# main.net
KiCad netlist of a schematic drawn in EAGLE
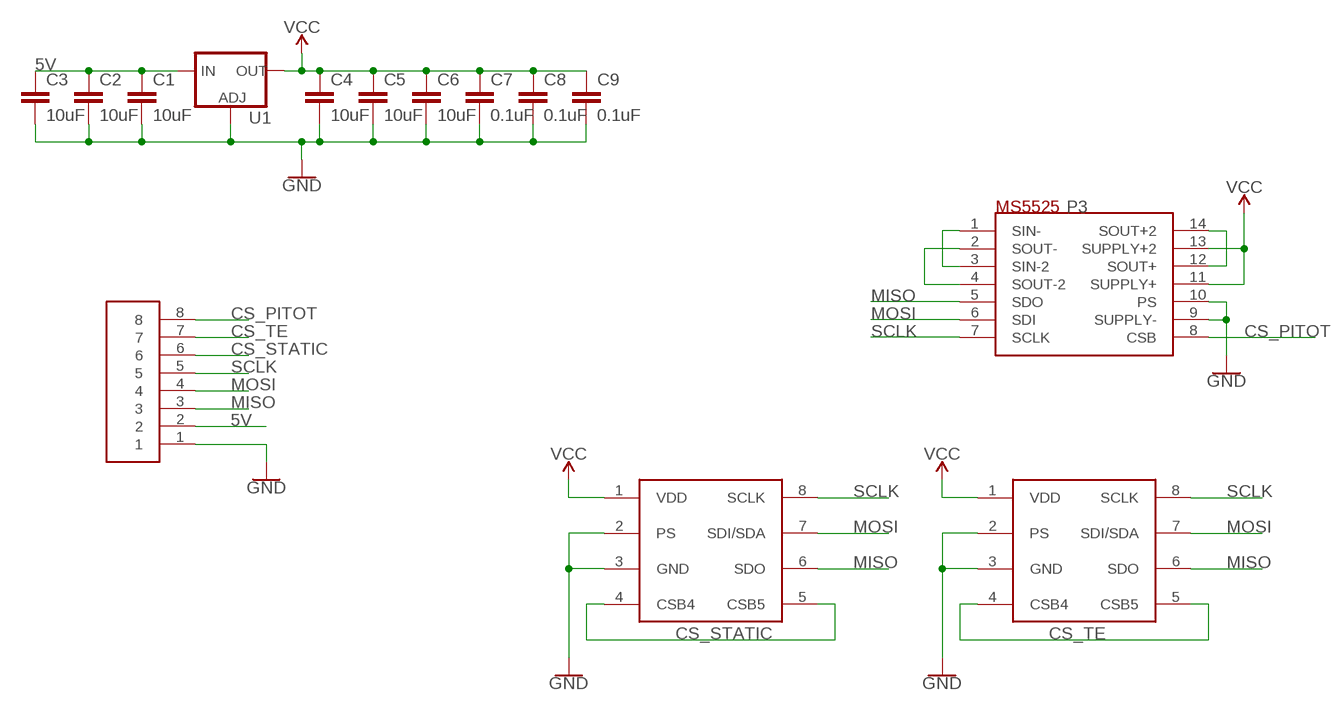
[diagram p0: schematic, sheet 1]

(export (version "E")
  (design (tool "Eeschema 10.0.6"))
  (components
    (comp (ref "C1")
      (value "10uF")
      (footprint "eagle-import:0805")
      (libsource (lib "eagle-import") (part "10UF-0805-10V-10%"))
    )
    (comp (ref "C2")
      (value "10uF")
      (footprint "eagle-import:0805")
      (libsource (lib "eagle-import") (part "10UF-0805-10V-10%"))
    )
    (comp (ref "C3")
      (value "10uF")
      (footprint "eagle-import:0805")
      (libsource (lib "eagle-import") (part "10UF-0805-10V-10%"))
    )
    (comp (ref "C4")
      (value "10uF")
      (footprint "eagle-import:0805")
      (libsource (lib "eagle-import") (part "10UF-0805-10V-10%"))
    )
    (comp (ref "C5")
      (value "10uF")
      (footprint "eagle-import:0805")
      (libsource (lib "eagle-import") (part "10UF-0805-10V-10%"))
    )
    (comp (ref "C6")
      (value "10uF")
      (footprint "eagle-import:0805")
      (libsource (lib "eagle-import") (part "10UF-0805-10V-10%"))
    )
    (comp (ref "C7")
      (value "0.1uF")
      (footprint "eagle-import:0603")
      (libsource (lib "eagle-import") (part "0.1UF-0603-25V-5%"))
    )
    (comp (ref "C8")
      (value "0.1uF")
      (footprint "eagle-import:0603")
      (libsource (lib "eagle-import") (part "0.1UF-0603-25V-5%"))
    )
    (comp (ref "C9")
      (value "0.1uF")
      (footprint "eagle-import:0603")
      (libsource (lib "eagle-import") (part "0.1UF-0603-25V-5%"))
    )
    (comp (ref "P1")
      (value "MS5611")
      (footprint "eagle-import:MS5611")
      (libsource (lib "eagle-import") (part "MS5611"))
    )
    (comp (ref "P2")
      (value "MS5611")
      (footprint "eagle-import:MS5611")
      (libsource (lib "eagle-import") (part "MS5611"))
    )
    (comp (ref "P3")
      (value "MS5525")
      (footprint "eagle-import:SOIC14-WIDE")
      (libsource (lib "eagle-import") (part "MS5525"))
    )
    (comp (ref "U$1")
      (value "HEADER8")
      (footprint "eagle-import:8PINVALULOK")
      (libsource (lib "eagle-import") (part "HEADER8"))
    )
    (comp (ref "U1")
      (value "V_REG_317SMD")
      (footprint "eagle-import:SOT223")
      (libsource (lib "eagle-import") (part "V_REG_317SMD"))
    )
  )
  (nets
    (net (code "1") (name "/5V") (class "Default")
      (node (ref "C1") (pin "1") (pinfunction "1_1") (pintype "passive"))
      (node (ref "C2") (pin "1") (pinfunction "1_1") (pintype "passive"))
      (node (ref "C3") (pin "1") (pinfunction "1_1") (pintype "passive"))
      (node (ref "U$1") (pin "2") (pinfunction "2_2") (pintype "bidirectional"))
      (node (ref "U1") (pin "3") (pinfunction "IN_3") (pintype "input"))
    )
    (net (code "2") (name "/CS_PITOT") (class "Default")
      (node (ref "P3") (pin "8") (pinfunction "CSB_8") (pintype "bidirectional"))
      (node (ref "U$1") (pin "8") (pinfunction "8_8") (pintype "bidirectional"))
    )
    (net (code "3") (name "/CS_STATIC") (class "Default")
      (node (ref "P1") (pin "4") (pinfunction "CSB4_4") (pintype "bidirectional"))
      (node (ref "P1") (pin "5") (pinfunction "CSB5_5") (pintype "bidirectional"))
      (node (ref "U$1") (pin "6") (pinfunction "6_6") (pintype "bidirectional"))
    )
    (net (code "4") (name "/CS_TE") (class "Default")
      (node (ref "P2") (pin "4") (pinfunction "CSB4_4") (pintype "bidirectional"))
      (node (ref "P2") (pin "5") (pinfunction "CSB5_5") (pintype "bidirectional"))
      (node (ref "U$1") (pin "7") (pinfunction "7_7") (pintype "bidirectional"))
    )
    (net (code "5") (name "/MISO") (class "Default")
      (node (ref "P1") (pin "6") (pinfunction "SDO_6") (pintype "bidirectional"))
      (node (ref "P2") (pin "6") (pinfunction "SDO_6") (pintype "bidirectional"))
      (node (ref "P3") (pin "5") (pinfunction "SDO_5") (pintype "bidirectional"))
      (node (ref "U$1") (pin "3") (pinfunction "3_3") (pintype "bidirectional"))
    )
    (net (code "6") (name "/MOSI") (class "Default")
      (node (ref "P1") (pin "7") (pinfunction "SDI/SDA_7") (pintype "bidirectional"))
      (node (ref "P2") (pin "7") (pinfunction "SDI/SDA_7") (pintype "bidirectional"))
      (node (ref "P3") (pin "6") (pinfunction "SDI_6") (pintype "bidirectional"))
      (node (ref "U$1") (pin "4") (pinfunction "4_4") (pintype "bidirectional"))
    )
    (net (code "7") (name "/SCLK") (class "Default")
      (node (ref "P1") (pin "8") (pinfunction "SCLK_8") (pintype "bidirectional"))
      (node (ref "P2") (pin "8") (pinfunction "SCLK_8") (pintype "bidirectional"))
      (node (ref "P3") (pin "7") (pinfunction "SCLK_7") (pintype "bidirectional"))
      (node (ref "U$1") (pin "5") (pinfunction "5_5") (pintype "bidirectional"))
    )
    (net (code "8") (name "GND") (class "Default")
      (node (ref "C1") (pin "2") (pinfunction "2_2") (pintype "passive"))
      (node (ref "C2") (pin "2") (pinfunction "2_2") (pintype "passive"))
      (node (ref "C3") (pin "2") (pinfunction "2_2") (pintype "passive"))
      (node (ref "C4") (pin "2") (pinfunction "2_2") (pintype "passive"))
      (node (ref "C5") (pin "2") (pinfunction "2_2") (pintype "passive"))
      (node (ref "C6") (pin "2") (pinfunction "2_2") (pintype "passive"))
      (node (ref "C7") (pin "2") (pinfunction "2_2") (pintype "passive"))
      (node (ref "C8") (pin "2") (pinfunction "2_2") (pintype "passive"))
      (node (ref "C9") (pin "2") (pinfunction "2_2") (pintype "passive"))
      (node (ref "P1") (pin "2") (pinfunction "PS_2") (pintype "bidirectional"))
      (node (ref "P1") (pin "3") (pinfunction "GND_3") (pintype "bidirectional"))
      (node (ref "P2") (pin "2") (pinfunction "PS_2") (pintype "bidirectional"))
      (node (ref "P2") (pin "3") (pinfunction "GND_3") (pintype "bidirectional"))
      (node (ref "P3") (pin "10") (pinfunction "PS_10") (pintype "bidirectional"))
      (node (ref "P3") (pin "9") (pinfunction "SUPPLY-_9") (pintype "bidirectional"))
      (node (ref "U$1") (pin "1") (pinfunction "1_1") (pintype "bidirectional"))
      (node (ref "U1") (pin "1") (pinfunction "ADJ_1") (pintype "input"))
    )
    (net (code "9") (name "Net-(P3-SIN-)") (class "Default")
      (node (ref "P3") (pin "1") (pinfunction "SIN-_1") (pintype "bidirectional"))
      (node (ref "P3") (pin "3") (pinfunction "SIN-2_3") (pintype "bidirectional"))
    )
    (net (code "10") (name "Net-(P3-SOUT+)") (class "Default")
      (node (ref "P3") (pin "12") (pinfunction "SOUT+_12") (pintype "bidirectional"))
      (node (ref "P3") (pin "14") (pinfunction "SOUT+2_14") (pintype "bidirectional"))
    )
    (net (code "11") (name "Net-(P3-SOUT-)") (class "Default")
      (node (ref "P3") (pin "2") (pinfunction "SOUT-_2") (pintype "bidirectional"))
      (node (ref "P3") (pin "4") (pinfunction "SOUT-2_4") (pintype "bidirectional"))
    )
    (net (code "12") (name "VCC") (class "Default")
      (node (ref "C4") (pin "1") (pinfunction "1_1") (pintype "passive"))
      (node (ref "C5") (pin "1") (pinfunction "1_1") (pintype "passive"))
      (node (ref "C6") (pin "1") (pinfunction "1_1") (pintype "passive"))
      (node (ref "C7") (pin "1") (pinfunction "1_1") (pintype "passive"))
      (node (ref "C8") (pin "1") (pinfunction "1_1") (pintype "passive"))
      (node (ref "C9") (pin "1") (pinfunction "1_1") (pintype "passive"))
      (node (ref "P1") (pin "1") (pinfunction "VDD_1") (pintype "bidirectional"))
      (node (ref "P2") (pin "1") (pinfunction "VDD_1") (pintype "bidirectional"))
      (node (ref "P3") (pin "11") (pinfunction "SUPPLY+_11") (pintype "bidirectional"))
      (node (ref "P3") (pin "13") (pinfunction "SUPPLY+2_13") (pintype "bidirectional"))
      (node (ref "U1") (pin "2") (pinfunction "OUT_2") (pintype "output"))
    )
  )
)
